# CentralBoard.net
KiCad netlist of a schematic drawn in EAGLE
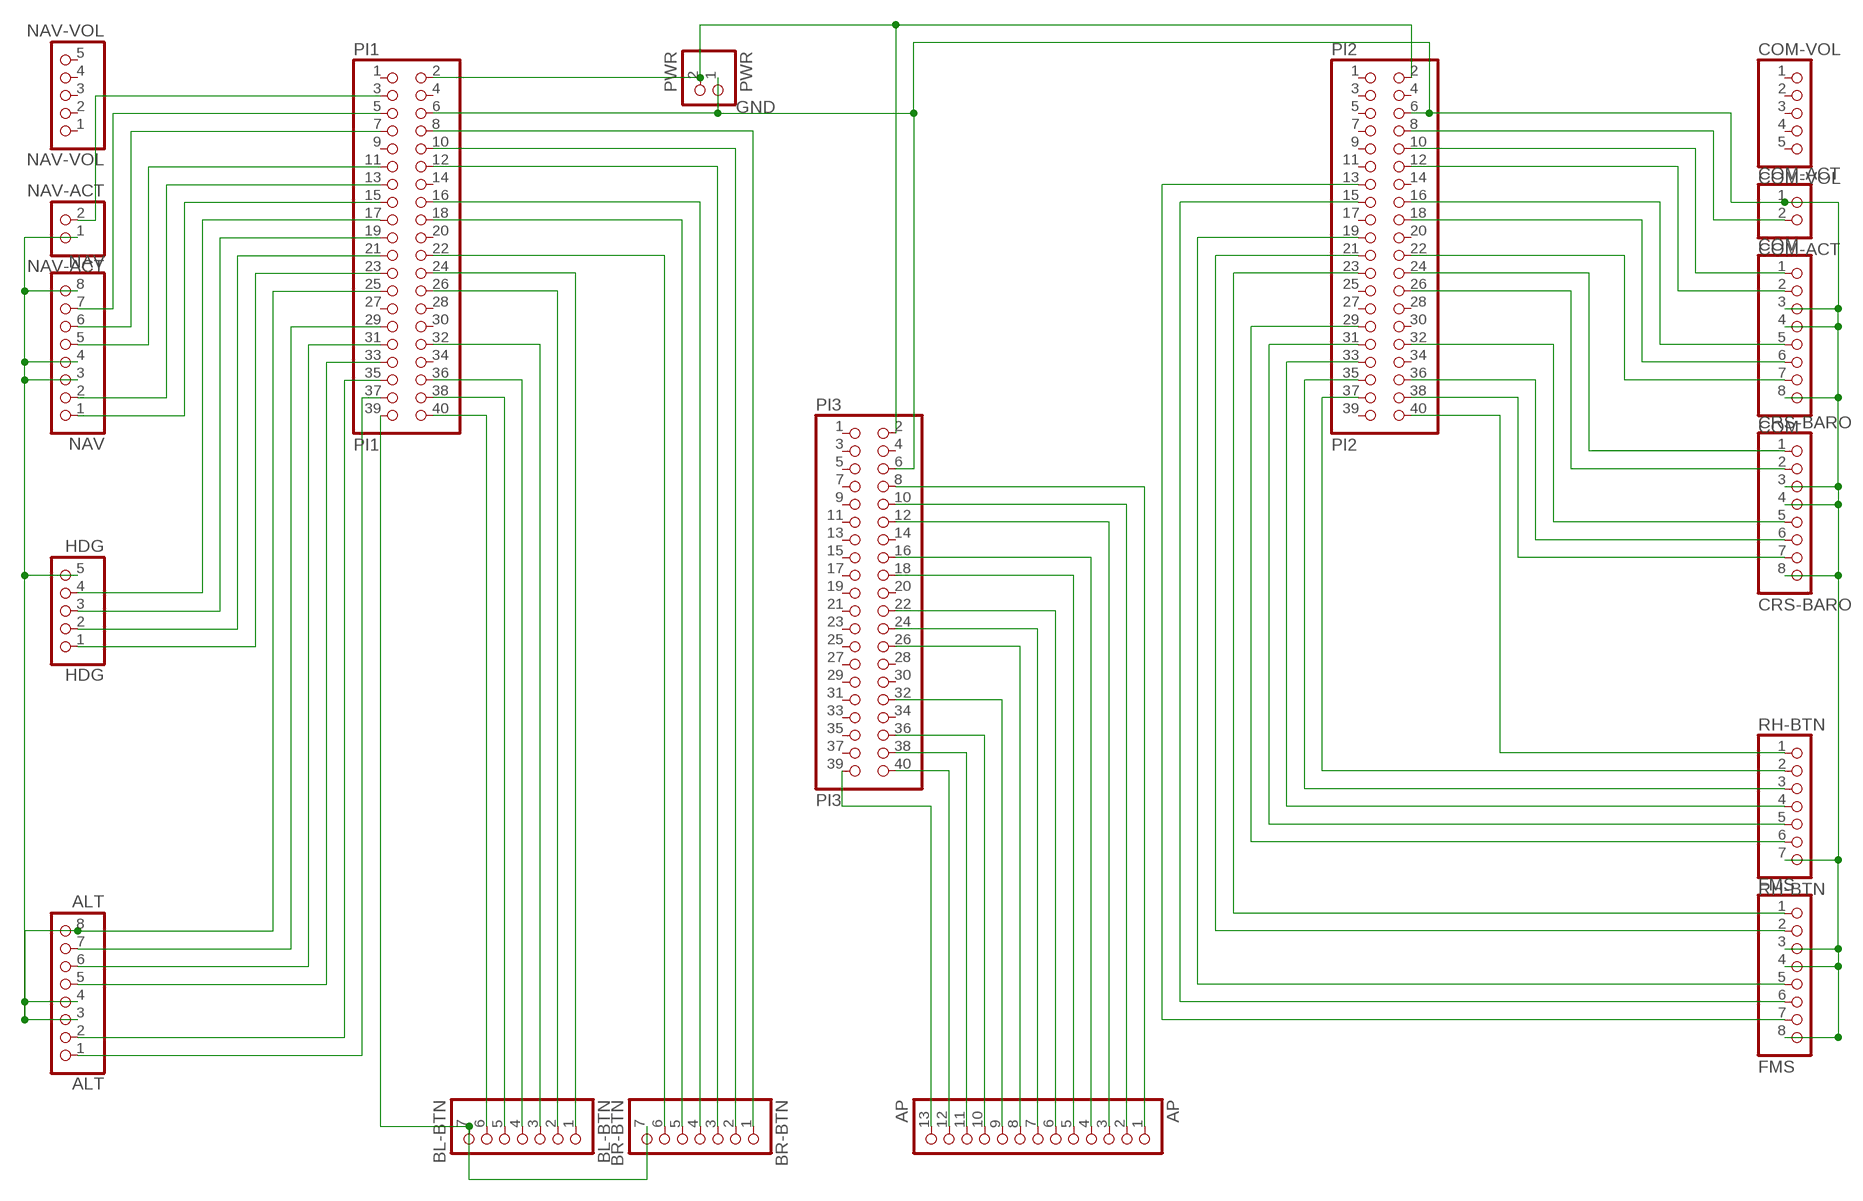
[diagram p0: schematic, sheet 1]

(export (version "E")
  (design (tool "Eeschema 10.0.6"))
  (components
    (comp (ref "ALT")
      (value "ALT")
      (footprint "eagle-import:1X08_90")
      (libsource (lib "eagle-import") (part "PINHD-1X8/90"))
    )
    (comp (ref "AP")
      (value "AP")
      (footprint "eagle-import:1X13")
      (libsource (lib "eagle-import") (part "PINHD-1X13"))
    )
    (comp (ref "BL-BTN")
      (value "BL-BTN")
      (footprint "eagle-import:1X07_90")
      (libsource (lib "eagle-import") (part "PINHD-1X7/90"))
    )
    (comp (ref "BR-BTN")
      (value "BR-BTN")
      (footprint "eagle-import:1X07")
      (libsource (lib "eagle-import") (part "PINHD-1X7"))
    )
    (comp (ref "COM")
      (value "COM")
      (footprint "eagle-import:1X08_90")
      (libsource (lib "eagle-import") (part "PINHD-1X8/90"))
    )
    (comp (ref "COM-ACT")
      (value "COM-ACT")
      (footprint "eagle-import:1X02_90")
      (libsource (lib "eagle-import") (part "PINHD-1X2/90"))
    )
    (comp (ref "COM-VOL")
      (value "COM-VOL")
      (footprint "eagle-import:1X05_90")
      (libsource (lib "eagle-import") (part "PINHD-1X5/90"))
    )
    (comp (ref "CRS-BARO")
      (value "CRS-BARO")
      (footprint "eagle-import:1X08_90")
      (libsource (lib "eagle-import") (part "PINHD-1X8/90"))
    )
    (comp (ref "FMS")
      (value "FMS")
      (footprint "eagle-import:1X08_90")
      (libsource (lib "eagle-import") (part "PINHD-1X8/90"))
    )
    (comp (ref "HDG")
      (value "HDG")
      (footprint "eagle-import:1X05_90")
      (libsource (lib "eagle-import") (part "PINHD-1X5/90"))
    )
    (comp (ref "NAV")
      (value "NAV")
      (footprint "eagle-import:1X08_90")
      (libsource (lib "eagle-import") (part "PINHD-1X8/90"))
    )
    (comp (ref "NAV-ACT")
      (value "NAV-ACT")
      (footprint "eagle-import:1X02_90")
      (libsource (lib "eagle-import") (part "PINHD-1X2/90"))
    )
    (comp (ref "NAV-VOL")
      (value "NAV-VOL")
      (footprint "eagle-import:1X05_90")
      (libsource (lib "eagle-import") (part "PINHD-1X5/90"))
    )
    (comp (ref "PI1")
      (value "PI1")
      (footprint "eagle-import:2X20")
      (libsource (lib "eagle-import") (part "PINHD-2X20"))
    )
    (comp (ref "PI2")
      (value "PI2")
      (footprint "eagle-import:2X20")
      (libsource (lib "eagle-import") (part "PINHD-2X20"))
    )
    (comp (ref "PI3")
      (value "PI3")
      (footprint "eagle-import:2X20")
      (libsource (lib "eagle-import") (part "PINHD-2X20"))
    )
    (comp (ref "PWR")
      (value "PWR")
      (footprint "eagle-import:1X02_90")
      (libsource (lib "eagle-import") (part "PINHD-1X2/90"))
    )
    (comp (ref "RH-BTN")
      (value "RH-BTN")
      (footprint "eagle-import:1X07_90")
      (libsource (lib "eagle-import") (part "PINHD-1X7/90"))
    )
  )
  (nets
    (net (code "1") (name "/GND") (class "Default")
      (node (ref "COM") (pin "3") (pinfunction "3_3") (pintype "passive"))
      (node (ref "COM") (pin "4") (pinfunction "4_4") (pintype "passive"))
      (node (ref "COM") (pin "8") (pinfunction "8_8") (pintype "passive"))
      (node (ref "COM-ACT") (pin "1") (pinfunction "1_1") (pintype "passive"))
      (node (ref "CRS-BARO") (pin "3") (pinfunction "3_3") (pintype "passive"))
      (node (ref "CRS-BARO") (pin "4") (pinfunction "4_4") (pintype "passive"))
      (node (ref "CRS-BARO") (pin "8") (pinfunction "8_8") (pintype "passive"))
      (node (ref "FMS") (pin "3") (pinfunction "3_3") (pintype "passive"))
      (node (ref "FMS") (pin "4") (pinfunction "4_4") (pintype "passive"))
      (node (ref "FMS") (pin "8") (pinfunction "8_8") (pintype "passive"))
      (node (ref "PI1") (pin "6") (pinfunction "6_6") (pintype "passive"))
      (node (ref "PI2") (pin "6") (pinfunction "6_6") (pintype "passive"))
      (node (ref "PI3") (pin "6") (pinfunction "6_6") (pintype "passive"))
      (node (ref "PWR") (pin "1") (pinfunction "1_1") (pintype "passive"))
      (node (ref "RH-BTN") (pin "7") (pinfunction "7_7") (pintype "passive"))
    )
    (net (code "2") (name "Net-(ALT-Pad1)") (class "Default")
      (node (ref "ALT") (pin "1") (pinfunction "1_1") (pintype "passive"))
      (node (ref "PI1") (pin "37") (pinfunction "37_37") (pintype "passive"))
    )
    (net (code "3") (name "Net-(ALT-Pad2)") (class "Default")
      (node (ref "ALT") (pin "2") (pinfunction "2_2") (pintype "passive"))
      (node (ref "PI1") (pin "35") (pinfunction "35_35") (pintype "passive"))
    )
    (net (code "4") (name "Net-(ALT-Pad3)") (class "Default")
      (node (ref "ALT") (pin "3") (pinfunction "3_3") (pintype "passive"))
      (node (ref "ALT") (pin "4") (pinfunction "4_4") (pintype "passive"))
      (node (ref "ALT") (pin "8") (pinfunction "8_8") (pintype "passive"))
      (node (ref "HDG") (pin "5") (pinfunction "5_5") (pintype "passive"))
      (node (ref "NAV") (pin "3") (pinfunction "3_3") (pintype "passive"))
      (node (ref "NAV") (pin "4") (pinfunction "4_4") (pintype "passive"))
      (node (ref "NAV") (pin "8") (pinfunction "8_8") (pintype "passive"))
      (node (ref "NAV-ACT") (pin "1") (pinfunction "1_1") (pintype "passive"))
      (node (ref "PI1") (pin "25") (pinfunction "25_25") (pintype "passive"))
    )
    (net (code "5") (name "Net-(ALT-Pad5)") (class "Default")
      (node (ref "ALT") (pin "5") (pinfunction "5_5") (pintype "passive"))
      (node (ref "PI1") (pin "33") (pinfunction "33_33") (pintype "passive"))
    )
    (net (code "6") (name "Net-(ALT-Pad6)") (class "Default")
      (node (ref "ALT") (pin "6") (pinfunction "6_6") (pintype "passive"))
      (node (ref "PI1") (pin "31") (pinfunction "31_31") (pintype "passive"))
    )
    (net (code "7") (name "Net-(ALT-Pad7)") (class "Default")
      (node (ref "ALT") (pin "7") (pinfunction "7_7") (pintype "passive"))
      (node (ref "PI1") (pin "29") (pinfunction "29_29") (pintype "passive"))
    )
    (net (code "8") (name "Net-(AP-Pad1)") (class "Default")
      (node (ref "AP") (pin "1") (pinfunction "1_1") (pintype "passive"))
      (node (ref "PI3") (pin "8") (pinfunction "8_8") (pintype "passive"))
    )
    (net (code "9") (name "Net-(AP-Pad2)") (class "Default")
      (node (ref "AP") (pin "2") (pinfunction "2_2") (pintype "passive"))
      (node (ref "PI3") (pin "10") (pinfunction "10_10") (pintype "passive"))
    )
    (net (code "10") (name "Net-(AP-Pad3)") (class "Default")
      (node (ref "AP") (pin "3") (pinfunction "3_3") (pintype "passive"))
      (node (ref "PI3") (pin "12") (pinfunction "12_12") (pintype "passive"))
    )
    (net (code "11") (name "Net-(AP-Pad4)") (class "Default")
      (node (ref "AP") (pin "4") (pinfunction "4_4") (pintype "passive"))
      (node (ref "PI3") (pin "16") (pinfunction "16_16") (pintype "passive"))
    )
    (net (code "12") (name "Net-(AP-Pad5)") (class "Default")
      (node (ref "AP") (pin "5") (pinfunction "5_5") (pintype "passive"))
      (node (ref "PI3") (pin "18") (pinfunction "18_18") (pintype "passive"))
    )
    (net (code "13") (name "Net-(AP-Pad6)") (class "Default")
      (node (ref "AP") (pin "6") (pinfunction "6_6") (pintype "passive"))
      (node (ref "PI3") (pin "22") (pinfunction "22_22") (pintype "passive"))
    )
    (net (code "14") (name "Net-(AP-Pad7)") (class "Default")
      (node (ref "AP") (pin "7") (pinfunction "7_7") (pintype "passive"))
      (node (ref "PI3") (pin "24") (pinfunction "24_24") (pintype "passive"))
    )
    (net (code "15") (name "Net-(AP-Pad8)") (class "Default")
      (node (ref "AP") (pin "8") (pinfunction "8_8") (pintype "passive"))
      (node (ref "PI3") (pin "26") (pinfunction "26_26") (pintype "passive"))
    )
    (net (code "16") (name "Net-(AP-Pad9)") (class "Default")
      (node (ref "AP") (pin "9") (pinfunction "9_9") (pintype "passive"))
      (node (ref "PI3") (pin "32") (pinfunction "32_32") (pintype "passive"))
    )
    (net (code "17") (name "Net-(AP-Pad10)") (class "Default")
      (node (ref "AP") (pin "10") (pinfunction "10_10") (pintype "passive"))
      (node (ref "PI3") (pin "36") (pinfunction "36_36") (pintype "passive"))
    )
    (net (code "18") (name "Net-(AP-Pad11)") (class "Default")
      (node (ref "AP") (pin "11") (pinfunction "11_11") (pintype "passive"))
      (node (ref "PI3") (pin "38") (pinfunction "38_38") (pintype "passive"))
    )
    (net (code "19") (name "Net-(AP-Pad12)") (class "Default")
      (node (ref "AP") (pin "12") (pinfunction "12_12") (pintype "passive"))
      (node (ref "PI3") (pin "40") (pinfunction "40_40") (pintype "passive"))
    )
    (net (code "20") (name "Net-(AP-Pad13)") (class "Default")
      (node (ref "AP") (pin "13") (pinfunction "13_13") (pintype "passive"))
      (node (ref "PI3") (pin "39") (pinfunction "39_39") (pintype "passive"))
    )
    (net (code "21") (name "Net-(BL-BTN-Pad1)") (class "Default")
      (node (ref "BL-BTN") (pin "1") (pinfunction "1_1") (pintype "passive"))
      (node (ref "PI1") (pin "24") (pinfunction "24_24") (pintype "passive"))
    )
    (net (code "22") (name "Net-(BL-BTN-Pad2)") (class "Default")
      (node (ref "BL-BTN") (pin "2") (pinfunction "2_2") (pintype "passive"))
      (node (ref "PI1") (pin "26") (pinfunction "26_26") (pintype "passive"))
    )
    (net (code "23") (name "Net-(BL-BTN-Pad3)") (class "Default")
      (node (ref "BL-BTN") (pin "3") (pinfunction "3_3") (pintype "passive"))
      (node (ref "PI1") (pin "32") (pinfunction "32_32") (pintype "passive"))
    )
    (net (code "24") (name "Net-(BL-BTN-Pad4)") (class "Default")
      (node (ref "BL-BTN") (pin "4") (pinfunction "4_4") (pintype "passive"))
      (node (ref "PI1") (pin "36") (pinfunction "36_36") (pintype "passive"))
    )
    (net (code "25") (name "Net-(BL-BTN-Pad5)") (class "Default")
      (node (ref "BL-BTN") (pin "5") (pinfunction "5_5") (pintype "passive"))
      (node (ref "PI1") (pin "38") (pinfunction "38_38") (pintype "passive"))
    )
    (net (code "26") (name "Net-(BL-BTN-Pad6)") (class "Default")
      (node (ref "BL-BTN") (pin "6") (pinfunction "6_6") (pintype "passive"))
      (node (ref "PI1") (pin "40") (pinfunction "40_40") (pintype "passive"))
    )
    (net (code "27") (name "Net-(BL-BTN-Pad7)") (class "Default")
      (node (ref "BL-BTN") (pin "7") (pinfunction "7_7") (pintype "passive"))
      (node (ref "BR-BTN") (pin "7") (pinfunction "7_7") (pintype "passive"))
      (node (ref "PI1") (pin "39") (pinfunction "39_39") (pintype "passive"))
    )
    (net (code "28") (name "Net-(BR-BTN-Pad1)") (class "Default")
      (node (ref "BR-BTN") (pin "1") (pinfunction "1_1") (pintype "passive"))
      (node (ref "PI1") (pin "8") (pinfunction "8_8") (pintype "passive"))
    )
    (net (code "29") (name "Net-(BR-BTN-Pad2)") (class "Default")
      (node (ref "BR-BTN") (pin "2") (pinfunction "2_2") (pintype "passive"))
      (node (ref "PI1") (pin "10") (pinfunction "10_10") (pintype "passive"))
    )
    (net (code "30") (name "Net-(BR-BTN-Pad3)") (class "Default")
      (node (ref "BR-BTN") (pin "3") (pinfunction "3_3") (pintype "passive"))
      (node (ref "PI1") (pin "12") (pinfunction "12_12") (pintype "passive"))
    )
    (net (code "31") (name "Net-(BR-BTN-Pad4)") (class "Default")
      (node (ref "BR-BTN") (pin "4") (pinfunction "4_4") (pintype "passive"))
      (node (ref "PI1") (pin "16") (pinfunction "16_16") (pintype "passive"))
    )
    (net (code "32") (name "Net-(BR-BTN-Pad5)") (class "Default")
      (node (ref "BR-BTN") (pin "5") (pinfunction "5_5") (pintype "passive"))
      (node (ref "PI1") (pin "18") (pinfunction "18_18") (pintype "passive"))
    )
    (net (code "33") (name "Net-(BR-BTN-Pad6)") (class "Default")
      (node (ref "BR-BTN") (pin "6") (pinfunction "6_6") (pintype "passive"))
      (node (ref "PI1") (pin "22") (pinfunction "22_22") (pintype "passive"))
    )
    (net (code "34") (name "Net-(COM-ACT-Pad2)") (class "Default")
      (node (ref "COM-ACT") (pin "2") (pinfunction "2_2") (pintype "passive"))
      (node (ref "PI2") (pin "8") (pinfunction "8_8") (pintype "passive"))
    )
    (net (code "35") (name "Net-(COM-Pad1)") (class "Default")
      (node (ref "COM") (pin "1") (pinfunction "1_1") (pintype "passive"))
      (node (ref "PI2") (pin "10") (pinfunction "10_10") (pintype "passive"))
    )
    (net (code "36") (name "Net-(COM-Pad2)") (class "Default")
      (node (ref "COM") (pin "2") (pinfunction "2_2") (pintype "passive"))
      (node (ref "PI2") (pin "12") (pinfunction "12_12") (pintype "passive"))
    )
    (net (code "37") (name "Net-(COM-Pad5)") (class "Default")
      (node (ref "COM") (pin "5") (pinfunction "5_5") (pintype "passive"))
      (node (ref "PI2") (pin "16") (pinfunction "16_16") (pintype "passive"))
    )
    (net (code "38") (name "Net-(COM-Pad6)") (class "Default")
      (node (ref "COM") (pin "6") (pinfunction "6_6") (pintype "passive"))
      (node (ref "PI2") (pin "18") (pinfunction "18_18") (pintype "passive"))
    )
    (net (code "39") (name "Net-(COM-Pad7)") (class "Default")
      (node (ref "COM") (pin "7") (pinfunction "7_7") (pintype "passive"))
      (node (ref "PI2") (pin "22") (pinfunction "22_22") (pintype "passive"))
    )
    (net (code "40") (name "Net-(CRS-BARO-Pad1)") (class "Default")
      (node (ref "CRS-BARO") (pin "1") (pinfunction "1_1") (pintype "passive"))
      (node (ref "PI2") (pin "24") (pinfunction "24_24") (pintype "passive"))
    )
    (net (code "41") (name "Net-(CRS-BARO-Pad2)") (class "Default")
      (node (ref "CRS-BARO") (pin "2") (pinfunction "2_2") (pintype "passive"))
      (node (ref "PI2") (pin "26") (pinfunction "26_26") (pintype "passive"))
    )
    (net (code "42") (name "Net-(CRS-BARO-Pad5)") (class "Default")
      (node (ref "CRS-BARO") (pin "5") (pinfunction "5_5") (pintype "passive"))
      (node (ref "PI2") (pin "32") (pinfunction "32_32") (pintype "passive"))
    )
    (net (code "43") (name "Net-(CRS-BARO-Pad6)") (class "Default")
      (node (ref "CRS-BARO") (pin "6") (pinfunction "6_6") (pintype "passive"))
      (node (ref "PI2") (pin "36") (pinfunction "36_36") (pintype "passive"))
    )
    (net (code "44") (name "Net-(CRS-BARO-Pad7)") (class "Default")
      (node (ref "CRS-BARO") (pin "7") (pinfunction "7_7") (pintype "passive"))
      (node (ref "PI2") (pin "38") (pinfunction "38_38") (pintype "passive"))
    )
    (net (code "45") (name "Net-(FMS-Pad1)") (class "Default")
      (node (ref "FMS") (pin "1") (pinfunction "1_1") (pintype "passive"))
      (node (ref "PI2") (pin "23") (pinfunction "23_23") (pintype "passive"))
    )
    (net (code "46") (name "Net-(FMS-Pad2)") (class "Default")
      (node (ref "FMS") (pin "2") (pinfunction "2_2") (pintype "passive"))
      (node (ref "PI2") (pin "21") (pinfunction "21_21") (pintype "passive"))
    )
    (net (code "47") (name "Net-(FMS-Pad5)") (class "Default")
      (node (ref "FMS") (pin "5") (pinfunction "5_5") (pintype "passive"))
      (node (ref "PI2") (pin "19") (pinfunction "19_19") (pintype "passive"))
    )
    (net (code "48") (name "Net-(FMS-Pad6)") (class "Default")
      (node (ref "FMS") (pin "6") (pinfunction "6_6") (pintype "passive"))
      (node (ref "PI2") (pin "15") (pinfunction "15_15") (pintype "passive"))
    )
    (net (code "49") (name "Net-(FMS-Pad7)") (class "Default")
      (node (ref "FMS") (pin "7") (pinfunction "7_7") (pintype "passive"))
      (node (ref "PI2") (pin "13") (pinfunction "13_13") (pintype "passive"))
    )
    (net (code "50") (name "Net-(HDG-Pad1)") (class "Default")
      (node (ref "HDG") (pin "1") (pinfunction "1_1") (pintype "passive"))
      (node (ref "PI1") (pin "23") (pinfunction "23_23") (pintype "passive"))
    )
    (net (code "51") (name "Net-(HDG-Pad2)") (class "Default")
      (node (ref "HDG") (pin "2") (pinfunction "2_2") (pintype "passive"))
      (node (ref "PI1") (pin "21") (pinfunction "21_21") (pintype "passive"))
    )
    (net (code "52") (name "Net-(HDG-Pad3)") (class "Default")
      (node (ref "HDG") (pin "3") (pinfunction "3_3") (pintype "passive"))
      (node (ref "PI1") (pin "19") (pinfunction "19_19") (pintype "passive"))
    )
    (net (code "53") (name "Net-(HDG-Pad4)") (class "Default")
      (node (ref "HDG") (pin "4") (pinfunction "4_4") (pintype "passive"))
      (node (ref "PI1") (pin "17") (pinfunction "17_17") (pintype "passive"))
    )
    (net (code "54") (name "Net-(NAV-ACT-Pad2)") (class "Default")
      (node (ref "NAV-ACT") (pin "2") (pinfunction "2_2") (pintype "passive"))
      (node (ref "PI1") (pin "3") (pinfunction "3_3") (pintype "passive"))
    )
    (net (code "55") (name "Net-(NAV-Pad1)") (class "Default")
      (node (ref "NAV") (pin "1") (pinfunction "1_1") (pintype "passive"))
      (node (ref "PI1") (pin "15") (pinfunction "15_15") (pintype "passive"))
    )
    (net (code "56") (name "Net-(NAV-Pad2)") (class "Default")
      (node (ref "NAV") (pin "2") (pinfunction "2_2") (pintype "passive"))
      (node (ref "PI1") (pin "13") (pinfunction "13_13") (pintype "passive"))
    )
    (net (code "57") (name "Net-(NAV-Pad5)") (class "Default")
      (node (ref "NAV") (pin "5") (pinfunction "5_5") (pintype "passive"))
      (node (ref "PI1") (pin "11") (pinfunction "11_11") (pintype "passive"))
    )
    (net (code "58") (name "Net-(NAV-Pad6)") (class "Default")
      (node (ref "NAV") (pin "6") (pinfunction "6_6") (pintype "passive"))
      (node (ref "PI1") (pin "7") (pinfunction "7_7") (pintype "passive"))
    )
    (net (code "59") (name "Net-(NAV-Pad7)") (class "Default")
      (node (ref "NAV") (pin "7") (pinfunction "7_7") (pintype "passive"))
      (node (ref "PI1") (pin "5") (pinfunction "5_5") (pintype "passive"))
    )
    (net (code "60") (name "Net-(PI1-Pad2)") (class "Default")
      (node (ref "PI1") (pin "2") (pinfunction "2_2") (pintype "passive"))
      (node (ref "PI2") (pin "2") (pinfunction "2_2") (pintype "passive"))
      (node (ref "PI3") (pin "2") (pinfunction "2_2") (pintype "passive"))
      (node (ref "PWR") (pin "2") (pinfunction "2_2") (pintype "passive"))
    )
    (net (code "61") (name "Net-(PI2-Pad29)") (class "Default")
      (node (ref "PI2") (pin "29") (pinfunction "29_29") (pintype "passive"))
      (node (ref "RH-BTN") (pin "6") (pinfunction "6_6") (pintype "passive"))
    )
    (net (code "62") (name "Net-(PI2-Pad31)") (class "Default")
      (node (ref "PI2") (pin "31") (pinfunction "31_31") (pintype "passive"))
      (node (ref "RH-BTN") (pin "5") (pinfunction "5_5") (pintype "passive"))
    )
    (net (code "63") (name "Net-(PI2-Pad33)") (class "Default")
      (node (ref "PI2") (pin "33") (pinfunction "33_33") (pintype "passive"))
      (node (ref "RH-BTN") (pin "4") (pinfunction "4_4") (pintype "passive"))
    )
    (net (code "64") (name "Net-(PI2-Pad35)") (class "Default")
      (node (ref "PI2") (pin "35") (pinfunction "35_35") (pintype "passive"))
      (node (ref "RH-BTN") (pin "3") (pinfunction "3_3") (pintype "passive"))
    )
    (net (code "65") (name "Net-(PI2-Pad37)") (class "Default")
      (node (ref "PI2") (pin "37") (pinfunction "37_37") (pintype "passive"))
      (node (ref "RH-BTN") (pin "2") (pinfunction "2_2") (pintype "passive"))
    )
    (net (code "66") (name "Net-(PI2-Pad40)") (class "Default")
      (node (ref "PI2") (pin "40") (pinfunction "40_40") (pintype "passive"))
      (node (ref "RH-BTN") (pin "1") (pinfunction "1_1") (pintype "passive"))
    )
    (net (code "67") (name "unconnected-(COM-VOL-Pad1)") (class "Default")
      (node (ref "COM-VOL") (pin "1") (pinfunction "1_1") (pintype "passive"))
    )
    (net (code "68") (name "unconnected-(COM-VOL-Pad2)") (class "Default")
      (node (ref "COM-VOL") (pin "2") (pinfunction "2_2") (pintype "passive"))
    )
    (net (code "69") (name "unconnected-(COM-VOL-Pad3)") (class "Default")
      (node (ref "COM-VOL") (pin "3") (pinfunction "3_3") (pintype "passive"))
    )
    (net (code "70") (name "unconnected-(COM-VOL-Pad4)") (class "Default")
      (node (ref "COM-VOL") (pin "4") (pinfunction "4_4") (pintype "passive"))
    )
    (net (code "71") (name "unconnected-(COM-VOL-Pad5)") (class "Default")
      (node (ref "COM-VOL") (pin "5") (pinfunction "5_5") (pintype "passive"))
    )
    (net (code "72") (name "unconnected-(NAV-VOL-Pad1)") (class "Default")
      (node (ref "NAV-VOL") (pin "1") (pinfunction "1_1") (pintype "passive"))
    )
    (net (code "73") (name "unconnected-(NAV-VOL-Pad2)") (class "Default")
      (node (ref "NAV-VOL") (pin "2") (pinfunction "2_2") (pintype "passive"))
    )
    (net (code "74") (name "unconnected-(NAV-VOL-Pad3)") (class "Default")
      (node (ref "NAV-VOL") (pin "3") (pinfunction "3_3") (pintype "passive"))
    )
    (net (code "75") (name "unconnected-(NAV-VOL-Pad4)") (class "Default")
      (node (ref "NAV-VOL") (pin "4") (pinfunction "4_4") (pintype "passive"))
    )
    (net (code "76") (name "unconnected-(NAV-VOL-Pad5)") (class "Default")
      (node (ref "NAV-VOL") (pin "5") (pinfunction "5_5") (pintype "passive"))
    )
    (net (code "77") (name "unconnected-(PI1-Pad1)") (class "Default")
      (node (ref "PI1") (pin "1") (pinfunction "1_1") (pintype "passive"))
    )
    (net (code "78") (name "unconnected-(PI1-Pad4)") (class "Default")
      (node (ref "PI1") (pin "4") (pinfunction "4_4") (pintype "passive"))
    )
    (net (code "79") (name "unconnected-(PI1-Pad9)") (class "Default")
      (node (ref "PI1") (pin "9") (pinfunction "9_9") (pintype "passive"))
    )
    (net (code "80") (name "unconnected-(PI1-Pad14)") (class "Default")
      (node (ref "PI1") (pin "14") (pinfunction "14_14") (pintype "passive"))
    )
    (net (code "81") (name "unconnected-(PI1-Pad20)") (class "Default")
      (node (ref "PI1") (pin "20") (pinfunction "20_20") (pintype "passive"))
    )
    (net (code "82") (name "unconnected-(PI1-Pad27)") (class "Default")
      (node (ref "PI1") (pin "27") (pinfunction "27_27") (pintype "passive"))
    )
    (net (code "83") (name "unconnected-(PI1-Pad28)") (class "Default")
      (node (ref "PI1") (pin "28") (pinfunction "28_28") (pintype "passive"))
    )
    (net (code "84") (name "unconnected-(PI1-Pad30)") (class "Default")
      (node (ref "PI1") (pin "30") (pinfunction "30_30") (pintype "passive"))
    )
    (net (code "85") (name "unconnected-(PI1-Pad34)") (class "Default")
      (node (ref "PI1") (pin "34") (pinfunction "34_34") (pintype "passive"))
    )
    (net (code "86") (name "unconnected-(PI2-Pad1)") (class "Default")
      (node (ref "PI2") (pin "1") (pinfunction "1_1") (pintype "passive"))
    )
    (net (code "87") (name "unconnected-(PI2-Pad3)") (class "Default")
      (node (ref "PI2") (pin "3") (pinfunction "3_3") (pintype "passive"))
    )
    (net (code "88") (name "unconnected-(PI2-Pad4)") (class "Default")
      (node (ref "PI2") (pin "4") (pinfunction "4_4") (pintype "passive"))
    )
    (net (code "89") (name "unconnected-(PI2-Pad5)") (class "Default")
      (node (ref "PI2") (pin "5") (pinfunction "5_5") (pintype "passive"))
    )
    (net (code "90") (name "unconnected-(PI2-Pad7)") (class "Default")
      (node (ref "PI2") (pin "7") (pinfunction "7_7") (pintype "passive"))
    )
    (net (code "91") (name "unconnected-(PI2-Pad9)") (class "Default")
      (node (ref "PI2") (pin "9") (pinfunction "9_9") (pintype "passive"))
    )
    (net (code "92") (name "unconnected-(PI2-Pad11)") (class "Default")
      (node (ref "PI2") (pin "11") (pinfunction "11_11") (pintype "passive"))
    )
    (net (code "93") (name "unconnected-(PI2-Pad14)") (class "Default")
      (node (ref "PI2") (pin "14") (pinfunction "14_14") (pintype "passive"))
    )
    (net (code "94") (name "unconnected-(PI2-Pad17)") (class "Default")
      (node (ref "PI2") (pin "17") (pinfunction "17_17") (pintype "passive"))
    )
    (net (code "95") (name "unconnected-(PI2-Pad20)") (class "Default")
      (node (ref "PI2") (pin "20") (pinfunction "20_20") (pintype "passive"))
    )
    (net (code "96") (name "unconnected-(PI2-Pad25)") (class "Default")
      (node (ref "PI2") (pin "25") (pinfunction "25_25") (pintype "passive"))
    )
    (net (code "97") (name "unconnected-(PI2-Pad27)") (class "Default")
      (node (ref "PI2") (pin "27") (pinfunction "27_27") (pintype "passive"))
    )
    (net (code "98") (name "unconnected-(PI2-Pad28)") (class "Default")
      (node (ref "PI2") (pin "28") (pinfunction "28_28") (pintype "passive"))
    )
    (net (code "99") (name "unconnected-(PI2-Pad30)") (class "Default")
      (node (ref "PI2") (pin "30") (pinfunction "30_30") (pintype "passive"))
    )
    (net (code "100") (name "unconnected-(PI2-Pad34)") (class "Default")
      (node (ref "PI2") (pin "34") (pinfunction "34_34") (pintype "passive"))
    )
    (net (code "101") (name "unconnected-(PI2-Pad39)") (class "Default")
      (node (ref "PI2") (pin "39") (pinfunction "39_39") (pintype "passive"))
    )
    (net (code "102") (name "unconnected-(PI3-Pad1)") (class "Default")
      (node (ref "PI3") (pin "1") (pinfunction "1_1") (pintype "passive"))
    )
    (net (code "103") (name "unconnected-(PI3-Pad3)") (class "Default")
      (node (ref "PI3") (pin "3") (pinfunction "3_3") (pintype "passive"))
    )
    (net (code "104") (name "unconnected-(PI3-Pad4)") (class "Default")
      (node (ref "PI3") (pin "4") (pinfunction "4_4") (pintype "passive"))
    )
    (net (code "105") (name "unconnected-(PI3-Pad5)") (class "Default")
      (node (ref "PI3") (pin "5") (pinfunction "5_5") (pintype "passive"))
    )
    (net (code "106") (name "unconnected-(PI3-Pad7)") (class "Default")
      (node (ref "PI3") (pin "7") (pinfunction "7_7") (pintype "passive"))
    )
    (net (code "107") (name "unconnected-(PI3-Pad9)") (class "Default")
      (node (ref "PI3") (pin "9") (pinfunction "9_9") (pintype "passive"))
    )
    (net (code "108") (name "unconnected-(PI3-Pad11)") (class "Default")
      (node (ref "PI3") (pin "11") (pinfunction "11_11") (pintype "passive"))
    )
    (net (code "109") (name "unconnected-(PI3-Pad13)") (class "Default")
      (node (ref "PI3") (pin "13") (pinfunction "13_13") (pintype "passive"))
    )
    (net (code "110") (name "unconnected-(PI3-Pad14)") (class "Default")
      (node (ref "PI3") (pin "14") (pinfunction "14_14") (pintype "passive"))
    )
    (net (code "111") (name "unconnected-(PI3-Pad15)") (class "Default")
      (node (ref "PI3") (pin "15") (pinfunction "15_15") (pintype "passive"))
    )
    (net (code "112") (name "unconnected-(PI3-Pad17)") (class "Default")
      (node (ref "PI3") (pin "17") (pinfunction "17_17") (pintype "passive"))
    )
    (net (code "113") (name "unconnected-(PI3-Pad19)") (class "Default")
      (node (ref "PI3") (pin "19") (pinfunction "19_19") (pintype "passive"))
    )
    (net (code "114") (name "unconnected-(PI3-Pad20)") (class "Default")
      (node (ref "PI3") (pin "20") (pinfunction "20_20") (pintype "passive"))
    )
    (net (code "115") (name "unconnected-(PI3-Pad21)") (class "Default")
      (node (ref "PI3") (pin "21") (pinfunction "21_21") (pintype "passive"))
    )
    (net (code "116") (name "unconnected-(PI3-Pad23)") (class "Default")
      (node (ref "PI3") (pin "23") (pinfunction "23_23") (pintype "passive"))
    )
    (net (code "117") (name "unconnected-(PI3-Pad25)") (class "Default")
      (node (ref "PI3") (pin "25") (pinfunction "25_25") (pintype "passive"))
    )
    (net (code "118") (name "unconnected-(PI3-Pad27)") (class "Default")
      (node (ref "PI3") (pin "27") (pinfunction "27_27") (pintype "passive"))
    )
    (net (code "119") (name "unconnected-(PI3-Pad28)") (class "Default")
      (node (ref "PI3") (pin "28") (pinfunction "28_28") (pintype "passive"))
    )
    (net (code "120") (name "unconnected-(PI3-Pad29)") (class "Default")
      (node (ref "PI3") (pin "29") (pinfunction "29_29") (pintype "passive"))
    )
    (net (code "121") (name "unconnected-(PI3-Pad30)") (class "Default")
      (node (ref "PI3") (pin "30") (pinfunction "30_30") (pintype "passive"))
    )
    (net (code "122") (name "unconnected-(PI3-Pad31)") (class "Default")
      (node (ref "PI3") (pin "31") (pinfunction "31_31") (pintype "passive"))
    )
    (net (code "123") (name "unconnected-(PI3-Pad33)") (class "Default")
      (node (ref "PI3") (pin "33") (pinfunction "33_33") (pintype "passive"))
    )
    (net (code "124") (name "unconnected-(PI3-Pad34)") (class "Default")
      (node (ref "PI3") (pin "34") (pinfunction "34_34") (pintype "passive"))
    )
    (net (code "125") (name "unconnected-(PI3-Pad35)") (class "Default")
      (node (ref "PI3") (pin "35") (pinfunction "35_35") (pintype "passive"))
    )
    (net (code "126") (name "unconnected-(PI3-Pad37)") (class "Default")
      (node (ref "PI3") (pin "37") (pinfunction "37_37") (pintype "passive"))
    )
  )
)
